# Power_Load_LEDs10mA.net
KiCad netlist of a schematic drawn in Altium Designer
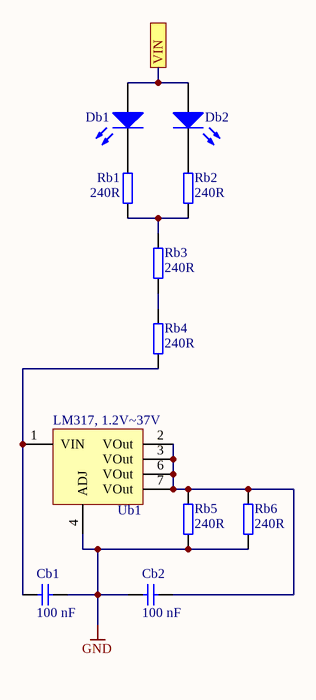
[diagram p0: Power_Load_LEDs10mA.SchDoc]

(export (version "E")
  (design (tool "Eeschema 10.0.6"))
  (components
    (comp (ref "Cb1")
      (value "100 nF")
      (footprint "C_0603_TE")
      (description "Generic capacitor")
      (fields
        (field (name "MANUFACTURER PART NUMBER") "UZgen_C_0603_100nF_50V_X7R")
        (field (name "MANUFACTURER") "UZgen")
        (field (name "CREATED FROM") "AGeiger")
      )
      (libsource (lib "user") (part "CAP-NP"))
    )
    (comp (ref "Cb2")
      (value "100 nF")
      (footprint "C_0603_TE")
      (description "Generic capacitor")
      (fields
        (field (name "MANUFACTURER PART NUMBER") "UZgen_C_0603_100nF_50V_X7R")
        (field (name "MANUFACTURER") "UZgen")
        (field (name "CREATED FROM") "AGeiger")
      )
      (libsource (lib "user") (part "CAP-NP"))
    )
    (comp (ref "Db1")
      (value "LED Blue")
      (footprint "WL-SMCW_0603")
      (fields
        (field (name "MANUFACTURER PART NUMBER") "LTST-C191TBKT")
        (field (name "MANUFACTURER") "LITE-ON Technology Corp.")
        (field (name "LCSC PART NUMBER") "C99290")
        (field (name "CREATED FROM") "UZgenTool")
      )
      (libsource (lib "user") (part "LED_Blue"))
    )
    (comp (ref "Db2")
      (value "LED Blue")
      (footprint "WL-SMCW_0603")
      (fields
        (field (name "MANUFACTURER PART NUMBER") "LTST-C191TBKT")
        (field (name "MANUFACTURER") "LITE-ON Technology Corp.")
        (field (name "LCSC PART NUMBER") "C99290")
        (field (name "CREATED FROM") "UZgenTool")
      )
      (libsource (lib "user") (part "LED_Blue"))
    )
    (comp (ref "Rb1")
      (value "240R")
      (footprint "R_0603_TE")
      (description "Generic resistor")
      (fields
        (field (name "MANUFACTURER PART NUMBER") "UZgen_R_0603_240R")
        (field (name "MANUFACTURER") "UZgen")
        (field (name "CREATED FROM") "UZgenTool")
      )
      (libsource (lib "user") (part "RES"))
    )
    (comp (ref "Rb2")
      (value "240R")
      (footprint "R_0603_TE")
      (description "Generic resistor")
      (fields
        (field (name "MANUFACTURER PART NUMBER") "UZgen_R_0603_240R")
        (field (name "MANUFACTURER") "UZgen")
        (field (name "CREATED FROM") "UZgenTool")
      )
      (libsource (lib "user") (part "RES"))
    )
    (comp (ref "Rb3")
      (value "240R")
      (footprint "R_0603_TE")
      (description "Generic resistor")
      (fields
        (field (name "MANUFACTURER PART NUMBER") "UZgen_R_0603_240R")
        (field (name "MANUFACTURER") "UZgen")
        (field (name "CREATED FROM") "UZgenTool")
      )
      (libsource (lib "user") (part "RES"))
    )
    (comp (ref "Rb4")
      (value "240R")
      (footprint "R_0603_TE")
      (description "Generic resistor")
      (fields
        (field (name "MANUFACTURER PART NUMBER") "UZgen_R_0603_240R")
        (field (name "MANUFACTURER") "UZgen")
        (field (name "CREATED FROM") "UZgenTool")
      )
      (libsource (lib "user") (part "RES"))
    )
    (comp (ref "Rb5")
      (value "240R")
      (footprint "R_0603_TE")
      (description "Generic resistor")
      (fields
        (field (name "MANUFACTURER PART NUMBER") "UZgen_R_0603_240R")
        (field (name "MANUFACTURER") "UZgen")
        (field (name "CREATED FROM") "UZgenTool")
      )
      (libsource (lib "user") (part "RES"))
    )
    (comp (ref "Rb6")
      (value "240R")
      (footprint "R_0603_TE")
      (description "Generic resistor")
      (fields
        (field (name "MANUFACTURER PART NUMBER") "UZgen_R_0603_240R")
        (field (name "MANUFACTURER") "UZgen")
        (field (name "CREATED FROM") "UZgenTool")
      )
      (libsource (lib "user") (part "RES"))
    )
    (comp (ref "Ub1")
      (value "LM317, 1.2V~37V")
      (footprint "SOIC127P600X175-8N")
      (fields
        (field (name "MANUFACTURER PART NUMBER") "LM317LD13TR")
        (field (name "MANUFACTURER") "STMicroelectronics")
        (field (name "LCSC PART NUMBER") "C81457")
        (field (name "CREATED FROM") "FRosner")
      )
      (libsource (lib "user") (part "LM317LD13TR"))
    )
  )
  (nets
    (net (code "1") (name "/VIN") (class "Default")
      (node (ref "Db1") (pin "2") (pinfunction "A_2") (pintype "passive"))
      (node (ref "Db2") (pin "2") (pinfunction "A_2") (pintype "passive"))
    )
    (net (code "2") (name "GND") (class "Default")
      (node (ref "Cb1") (pin "1") (pinfunction "1_1") (pintype "passive"))
      (node (ref "Cb2") (pin "2") (pinfunction "2_2") (pintype "passive"))
      (node (ref "Rb5") (pin "1") (pinfunction "1_1") (pintype "passive"))
      (node (ref "Rb6") (pin "2") (pinfunction "2_2") (pintype "passive"))
      (node (ref "Ub1") (pin "4") (pinfunction "ADJ_4") (pintype "power_in"))
    )
    (net (code "3") (name "Net-(Cb2-Pad1)") (class "Default")
      (node (ref "Cb2") (pin "1") (pinfunction "1_1") (pintype "passive"))
      (node (ref "Rb5") (pin "2") (pinfunction "2_2") (pintype "passive"))
      (node (ref "Rb6") (pin "1") (pinfunction "1_1") (pintype "passive"))
      (node (ref "Ub1") (pin "2") (pinfunction "VOut_2") (pintype "power_in"))
      (node (ref "Ub1") (pin "3") (pinfunction "VOut_3") (pintype "power_in"))
      (node (ref "Ub1") (pin "6") (pinfunction "VOut_6") (pintype "power_in"))
      (node (ref "Ub1") (pin "7") (pinfunction "VOut_7") (pintype "power_in"))
    )
    (net (code "4") (name "Net-(Db1-K)") (class "Default")
      (node (ref "Db1") (pin "1") (pinfunction "K_1") (pintype "passive"))
      (node (ref "Rb1") (pin "2") (pinfunction "2_2") (pintype "passive"))
    )
    (net (code "5") (name "Net-(Db2-K)") (class "Default")
      (node (ref "Db2") (pin "1") (pinfunction "K_1") (pintype "passive"))
      (node (ref "Rb2") (pin "1") (pinfunction "1_1") (pintype "passive"))
    )
    (net (code "6") (name "Net-(Rb1-Pad1)") (class "Default")
      (node (ref "Rb1") (pin "1") (pinfunction "1_1") (pintype "passive"))
      (node (ref "Rb2") (pin "2") (pinfunction "2_2") (pintype "passive"))
      (node (ref "Rb3") (pin "2") (pinfunction "2_2") (pintype "passive"))
    )
    (net (code "7") (name "Net-(Rb3-Pad1)") (class "Default")
      (node (ref "Rb3") (pin "1") (pinfunction "1_1") (pintype "passive"))
      (node (ref "Rb4") (pin "1") (pinfunction "1_1") (pintype "passive"))
    )
    (net (code "8") (name "Net-(Ub1-VIN)") (class "Default")
      (node (ref "Cb1") (pin "2") (pinfunction "2_2") (pintype "passive"))
      (node (ref "Rb4") (pin "2") (pinfunction "2_2") (pintype "passive"))
      (node (ref "Ub1") (pin "1") (pinfunction "VIN_1") (pintype "power_in"))
    )
  )
)
